# mcu.net
KiCad netlist of a schematic drawn in Altium Designer
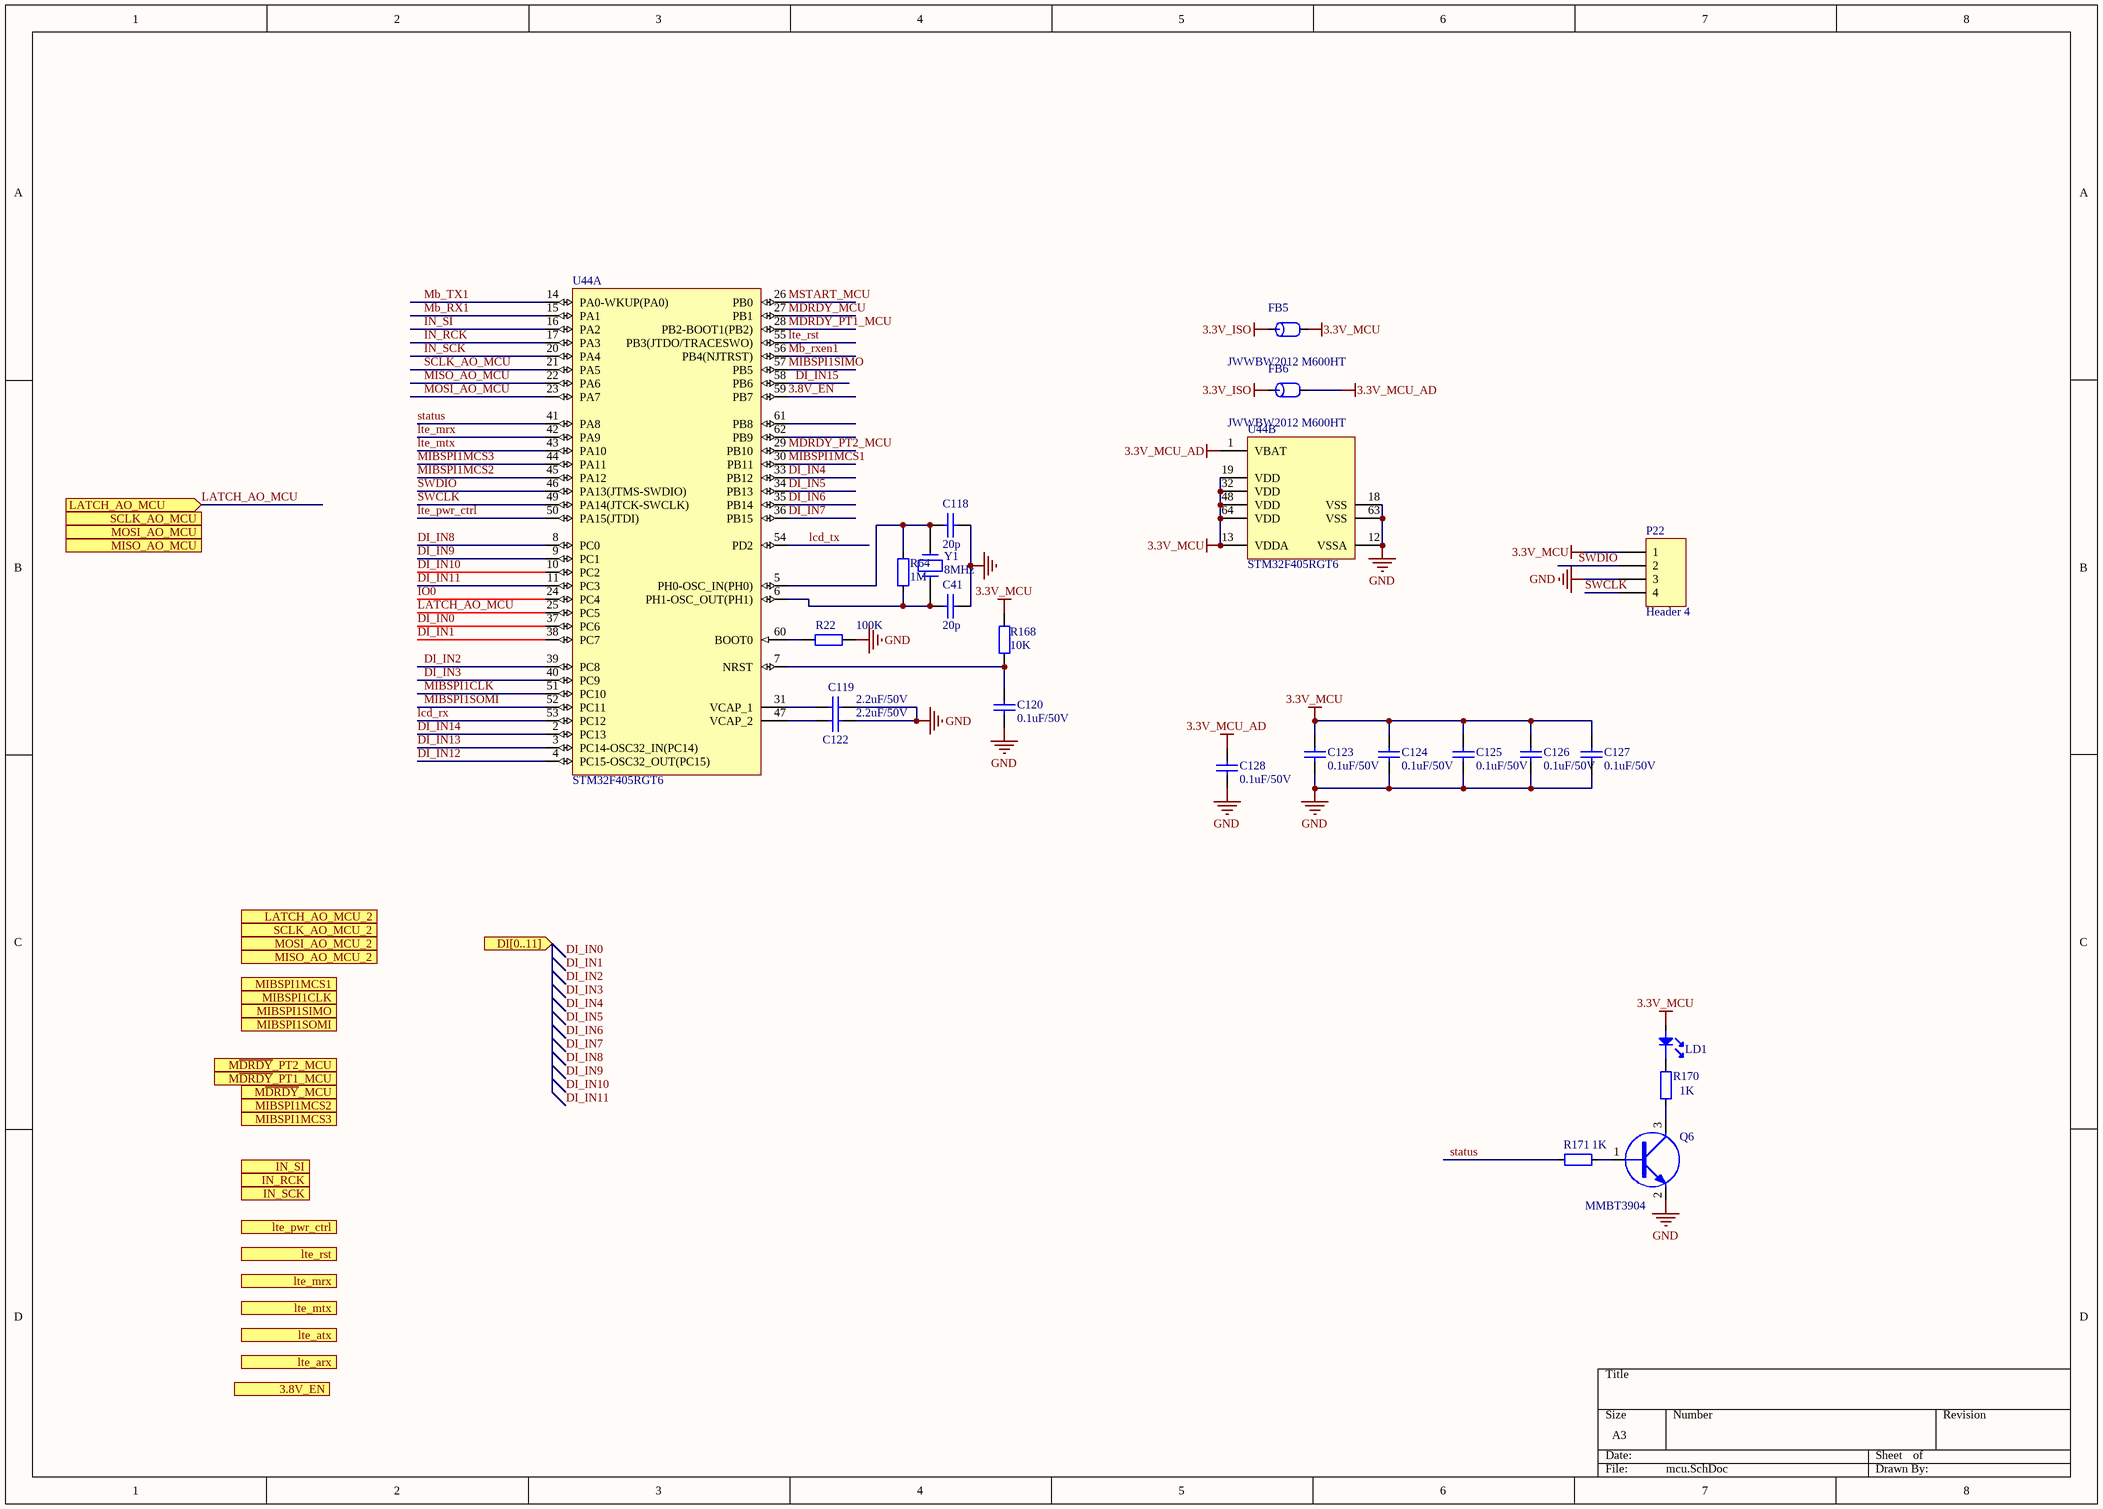
[diagram p0: mcu.SchDoc]

(export (version "E")
  (design (tool "Eeschema 10.0.6"))
  (components
    (comp (ref "C41")
      (value "20p")
      (footprint "0603c")
      (description "Capacitor")
      (libsource (lib "Schlib") (part "CAP"))
    )
    (comp (ref "C118")
      (value "20p")
      (footprint "0603c")
      (description "Capacitor")
      (libsource (lib "Schlib") (part "CAP"))
    )
    (comp (ref "C119")
      (value "2.2uF/50V")
      (footprint "0603C")
      (description "Capacitor")
      (fields (field (name "PUBLISHER") "Altium Limited"))
      (libsource (lib "Miscellaneous Devices") (part "Cap"))
    )
    (comp (ref "C120")
      (value "0.1uF/50V")
      (footprint "0603C")
      (description "Capacitor")
      (fields (field (name "PUBLISHER") "Altium Limited"))
      (libsource (lib "Miscellaneous Devices") (part "Cap"))
    )
    (comp (ref "C122")
      (value "2.2uF/50V")
      (footprint "0603C")
      (description "Capacitor")
      (fields (field (name "PUBLISHER") "Altium Limited"))
      (libsource (lib "Miscellaneous Devices") (part "Cap"))
    )
    (comp (ref "C123")
      (value "0.1uF/50V")
      (footprint "0603C")
      (description "Capacitor")
      (fields (field (name "PUBLISHER") "Altium Limited"))
      (libsource (lib "Miscellaneous Devices") (part "Cap"))
    )
    (comp (ref "C124")
      (value "0.1uF/50V")
      (footprint "0603C")
      (description "Capacitor")
      (fields (field (name "PUBLISHER") "Altium Limited"))
      (libsource (lib "Miscellaneous Devices") (part "Cap"))
    )
    (comp (ref "C125")
      (value "0.1uF/50V")
      (footprint "0603C")
      (description "Capacitor")
      (fields (field (name "PUBLISHER") "Altium Limited"))
      (libsource (lib "Miscellaneous Devices") (part "Cap"))
    )
    (comp (ref "C126")
      (value "0.1uF/50V")
      (footprint "0603C")
      (description "Capacitor")
      (fields (field (name "PUBLISHER") "Altium Limited"))
      (libsource (lib "Miscellaneous Devices") (part "Cap"))
    )
    (comp (ref "C127")
      (value "0.1uF/50V")
      (footprint "0603C")
      (description "Capacitor")
      (fields (field (name "PUBLISHER") "Altium Limited"))
      (libsource (lib "Miscellaneous Devices") (part "Cap"))
    )
    (comp (ref "C128")
      (value "0.1uF/50V")
      (footprint "0603C")
      (description "Capacitor")
      (fields (field (name "PUBLISHER") "Altium Limited"))
      (libsource (lib "Miscellaneous Devices") (part "Cap"))
    )
    (comp (ref "FB5")
      (value "JWWBW2012 M600HT")
      (footprint "0805R")
      (libsource (lib "Schlib_20110825") (part "FB"))
    )
    (comp (ref "FB6")
      (value "JWWBW2012 M600HT")
      (footprint "0805R")
      (libsource (lib "Schlib_20110825") (part "FB"))
    )
    (comp (ref "LD1")
      (value "LED_Green_19-217")
      (footprint "0603led")
      (libsource (lib "RC_M_D_00") (part "LED_Green_19-217"))
    )
    (comp (ref "P22")
      (value "Header 4")
      (footprint "HDR1X4")
      (description "Header, 4-Pin")
      (fields (field (name "PUBLISHER") "Altium Limited"))
      (libsource (lib "Miscellaneous Connectors") (part "Header 4"))
    )
    (comp (ref "Q6")
      (value "MMBT3904")
      (footprint "SOT23-3")
      (libsource (lib "CenLib") (part "NPN_MMBT3904"))
    )
    (comp (ref "R22") (value "100K") (footprint "0603R") (libsource (lib "") (part "Res0805M_1")))
    (comp (ref "R64") (value "1M") (footprint "0603R") (libsource (lib "RC_M_D_00") (part "RES0603")))
    (comp (ref "R168") (value "10K") (footprint "0603R") (libsource (lib "MQlibrary") (part "Res0805M")))
    (comp (ref "R170") (value "1K") (footprint "0603r") (libsource (lib "RC_M_D_00") (part "RES0603")))
    (comp (ref "R171") (value "1K") (footprint "0603r") (libsource (lib "RC_M_D_00") (part "RES0603")))
    (comp (ref "U44")
      (value "STM32F405RGT6")
      (footprint "LQFP-64")
      (fields (field (name "MANUFACTURER") "STMicroelectronics"))
      (libsource (lib "STMicroelectronics STM32 F4") (part "STM32F405RGT6"))
    )
    (comp (ref "Y1")
      (value "8MHz")
      (footprint "CRAY_5032")
      (description "HC49S-8MHz")
      (libsource (lib "*") (part "CRYSTAL"))
    )
  )
  (nets
    (net (code "13") (name "/3.8V_EN") (class "Default")
      (node (ref "U44") (pin "59") (pinfunction "PB7_59") (pintype "bidirectional"))
    )
    (net (code "15") (name "/DI_IN0") (class "Default")
      (node (ref "U44") (pin "37") (pinfunction "PC6_37") (pintype "bidirectional"))
    )
    (net (code "16") (name "/DI_IN1") (class "Default")
      (node (ref "U44") (pin "38") (pinfunction "PC7_38") (pintype "bidirectional"))
    )
    (net (code "17") (name "/DI_IN2") (class "Default")
      (node (ref "U44") (pin "39") (pinfunction "PC8_39") (pintype "bidirectional"))
    )
    (net (code "18") (name "/DI_IN3") (class "Default")
      (node (ref "U44") (pin "40") (pinfunction "PC9_40") (pintype "bidirectional"))
    )
    (net (code "19") (name "/DI_IN4") (class "Default")
      (node (ref "U44") (pin "33") (pinfunction "PB12_33") (pintype "bidirectional"))
    )
    (net (code "20") (name "/DI_IN5") (class "Default")
      (node (ref "U44") (pin "34") (pinfunction "PB13_34") (pintype "bidirectional"))
    )
    (net (code "21") (name "/DI_IN6") (class "Default")
      (node (ref "U44") (pin "35") (pinfunction "PB14_35") (pintype "bidirectional"))
    )
    (net (code "22") (name "/DI_IN7") (class "Default")
      (node (ref "U44") (pin "36") (pinfunction "PB15_36") (pintype "bidirectional"))
    )
    (net (code "23") (name "/DI_IN8") (class "Default")
      (node (ref "U44") (pin "8") (pinfunction "PC0_8") (pintype "bidirectional"))
    )
    (net (code "24") (name "/DI_IN9") (class "Default")
      (node (ref "U44") (pin "9") (pinfunction "PC1_9") (pintype "bidirectional"))
    )
    (net (code "25") (name "/DI_IN10") (class "Default")
      (node (ref "U44") (pin "10") (pinfunction "PC2_10") (pintype "bidirectional"))
    )
    (net (code "26") (name "/DI_IN11") (class "Default")
      (node (ref "U44") (pin "11") (pinfunction "PC3_11") (pintype "bidirectional"))
    )
    (net (code "27") (name "/DI_IN12") (class "Default")
      (node (ref "U44") (pin "4") (pinfunction "PC15-OSC32_OUT(PC15)_4") (pintype "bidirectional"))
    )
    (net (code "28") (name "/DI_IN13") (class "Default")
      (node (ref "U44") (pin "3") (pinfunction "PC14-OSC32_IN(PC14)_3") (pintype "bidirectional"))
    )
    (net (code "29") (name "/DI_IN14") (class "Default")
      (node (ref "U44") (pin "2") (pinfunction "PC13_2") (pintype "bidirectional"))
    )
    (net (code "30") (name "/DI_IN15") (class "Default")
      (node (ref "U44") (pin "58") (pinfunction "PB6_58") (pintype "bidirectional"))
    )
    (net (code "31") (name "/IN_RCK") (class "Default")
      (node (ref "U44") (pin "17") (pinfunction "PA3_17") (pintype "bidirectional"))
    )
    (net (code "32") (name "/IN_SCK") (class "Default")
      (node (ref "U44") (pin "20") (pinfunction "PA4_20") (pintype "bidirectional"))
    )
    (net (code "33") (name "/IN_SI") (class "Default")
      (node (ref "U44") (pin "16") (pinfunction "PA2_16") (pintype "bidirectional"))
    )
    (net (code "34") (name "/IO0") (class "Default")
      (node (ref "U44") (pin "24") (pinfunction "PC4_24") (pintype "bidirectional"))
    )
    (net (code "35") (name "/LATCH_AO_MCU") (class "Default")
      (node (ref "U44") (pin "25") (pinfunction "PC5_25") (pintype "bidirectional"))
    )
    (net (code "37") (name "/MIBSPI1CLK") (class "Default")
      (node (ref "U44") (pin "51") (pinfunction "PC10_51") (pintype "bidirectional"))
    )
    (net (code "38") (name "/MIBSPI1MCS1") (class "Default")
      (node (ref "U44") (pin "30") (pinfunction "PB11_30") (pintype "bidirectional"))
    )
    (net (code "39") (name "/MIBSPI1MCS2") (class "Default")
      (node (ref "U44") (pin "45") (pinfunction "PA12_45") (pintype "bidirectional"))
    )
    (net (code "40") (name "/MIBSPI1MCS3") (class "Default")
      (node (ref "U44") (pin "44") (pinfunction "PA11_44") (pintype "bidirectional"))
    )
    (net (code "41") (name "/MIBSPI1SIMO") (class "Default")
      (node (ref "U44") (pin "57") (pinfunction "PB5_57") (pintype "bidirectional"))
    )
    (net (code "42") (name "/MIBSPI1SOMI") (class "Default")
      (node (ref "U44") (pin "52") (pinfunction "PC11_52") (pintype "bidirectional"))
    )
    (net (code "43") (name "/MISO_AO_MCU") (class "Default")
      (node (ref "U44") (pin "22") (pinfunction "PA6_22") (pintype "bidirectional"))
    )
    (net (code "45") (name "/MOSI_AO_MCU") (class "Default")
      (node (ref "U44") (pin "23") (pinfunction "PA7_23") (pintype "bidirectional"))
    )
    (net (code "47") (name "/MSTART_MCU") (class "Default")
      (node (ref "U44") (pin "26") (pinfunction "PB0_26") (pintype "bidirectional"))
    )
    (net (code "48") (name "/Mb_RX1") (class "Default")
      (node (ref "U44") (pin "15") (pinfunction "PA1_15") (pintype "bidirectional"))
    )
    (net (code "49") (name "/Mb_TX1") (class "Default")
      (node (ref "U44") (pin "14") (pinfunction "PA0-WKUP(PA0)_14") (pintype "bidirectional"))
    )
    (net (code "50") (name "/Mb_rxen1") (class "Default")
      (node (ref "U44") (pin "56") (pinfunction "PB4(NJTRST)_56") (pintype "bidirectional"))
    )
    (net (code "51") (name "/M~{DRDY}_MCU") (class "Default")
      (node (ref "U44") (pin "27") (pinfunction "PB1_27") (pintype "bidirectional"))
    )
    (net (code "52") (name "/M~{DRDY}_PT1_MCU") (class "Default")
      (node (ref "U44") (pin "28") (pinfunction "PB2-BOOT1(PB2)_28") (pintype "bidirectional"))
    )
    (net (code "53") (name "/M~{DRDY}_PT2_MCU") (class "Default")
      (node (ref "U44") (pin "29") (pinfunction "PB10_29") (pintype "bidirectional"))
    )
    (net (code "54") (name "/SCLK_AO_MCU") (class "Default")
      (node (ref "U44") (pin "21") (pinfunction "PA5_21") (pintype "bidirectional"))
    )
    (net (code "56") (name "/SWCLK") (class "Default")
      (node (ref "P22") (pin "4") (pinfunction "4_4") (pintype "passive"))
      (node (ref "U44") (pin "49") (pinfunction "PA14(JTCK-SWCLK)_49") (pintype "bidirectional"))
    )
    (net (code "57") (name "/SWDIO") (class "Default")
      (node (ref "P22") (pin "2") (pinfunction "2_2") (pintype "passive"))
      (node (ref "U44") (pin "46") (pinfunction "PA13(JTMS-SWDIO)_46") (pintype "bidirectional"))
    )
    (net (code "58") (name "/lcd_rx") (class "Default")
      (node (ref "U44") (pin "53") (pinfunction "PC12_53") (pintype "bidirectional"))
    )
    (net (code "59") (name "/lcd_tx") (class "Default")
      (node (ref "U44") (pin "54") (pinfunction "PD2_54") (pintype "bidirectional"))
    )
    (net (code "62") (name "/lte_mrx") (class "Default")
      (node (ref "U44") (pin "42") (pinfunction "PA9_42") (pintype "bidirectional"))
    )
    (net (code "63") (name "/lte_mtx") (class "Default")
      (node (ref "U44") (pin "43") (pinfunction "PA10_43") (pintype "bidirectional"))
    )
    (net (code "64") (name "/lte_pwr_ctrl") (class "Default")
      (node (ref "U44") (pin "50") (pinfunction "PA15(JTDI)_50") (pintype "bidirectional"))
    )
    (net (code "65") (name "/lte_rst") (class "Default")
      (node (ref "U44") (pin "55") (pinfunction "PB3(JTDO/TRACESWO)_55") (pintype "bidirectional"))
    )
    (net (code "66") (name "/status") (class "Default")
      (node (ref "R171") (pin "1") (pinfunction "1_1") (pintype "passive"))
      (node (ref "U44") (pin "41") (pinfunction "PA8_41") (pintype "bidirectional"))
    )
    (net (code "67") (name "3.3V_ISO") (class "Default")
      (node (ref "FB5") (pin "1") (pintype "passive"))
      (node (ref "FB6") (pin "1") (pintype "passive"))
    )
    (net (code "68") (name "3.3V_MCU") (class "Default")
      (node (ref "C123") (pin "2") (pinfunction "2_2") (pintype "passive"))
      (node (ref "C124") (pin "2") (pinfunction "2_2") (pintype "passive"))
      (node (ref "C125") (pin "2") (pinfunction "2_2") (pintype "passive"))
      (node (ref "C126") (pin "2") (pinfunction "2_2") (pintype "passive"))
      (node (ref "C127") (pin "2") (pinfunction "2_2") (pintype "passive"))
      (node (ref "FB5") (pin "2") (pintype "passive"))
      (node (ref "LD1") (pin "1") (pinfunction "1_1") (pintype "passive"))
      (node (ref "P22") (pin "1") (pinfunction "1_1") (pintype "passive"))
      (node (ref "R168") (pin "2") (pinfunction "2_2") (pintype "passive"))
      (node (ref "U44") (pin "13") (pinfunction "VDDA_13") (pintype "power_in"))
      (node (ref "U44") (pin "19") (pinfunction "VDD_19") (pintype "power_in"))
      (node (ref "U44") (pin "32") (pinfunction "VDD_32") (pintype "power_in"))
      (node (ref "U44") (pin "48") (pinfunction "VDD_48") (pintype "power_in"))
      (node (ref "U44") (pin "64") (pinfunction "VDD_64") (pintype "power_in"))
    )
    (net (code "69") (name "3.3V_MCU_AD") (class "Default")
      (node (ref "C128") (pin "2") (pinfunction "2_2") (pintype "passive"))
      (node (ref "FB6") (pin "2") (pintype "passive"))
      (node (ref "U44") (pin "1") (pinfunction "VBAT_1") (pintype "power_in"))
    )
    (net (code "70") (name "GND") (class "Default")
      (node (ref "C118") (pin "1") (pinfunction "1_1") (pintype "passive"))
      (node (ref "C119") (pin "1") (pinfunction "1_1") (pintype "passive"))
      (node (ref "C120") (pin "1") (pinfunction "1_1") (pintype "passive"))
      (node (ref "C122") (pin "1") (pinfunction "1_1") (pintype "passive"))
      (node (ref "C123") (pin "1") (pinfunction "1_1") (pintype "passive"))
      (node (ref "C124") (pin "1") (pinfunction "1_1") (pintype "passive"))
      (node (ref "C125") (pin "1") (pinfunction "1_1") (pintype "passive"))
      (node (ref "C126") (pin "1") (pinfunction "1_1") (pintype "passive"))
      (node (ref "C127") (pin "1") (pinfunction "1_1") (pintype "passive"))
      (node (ref "C128") (pin "1") (pinfunction "1_1") (pintype "passive"))
      (node (ref "C41") (pin "1") (pinfunction "1_1") (pintype "passive"))
      (node (ref "P22") (pin "3") (pinfunction "3_3") (pintype "passive"))
      (node (ref "Q6") (pin "2") (pinfunction "E_2") (pintype "passive"))
      (node (ref "R22") (pin "2") (pinfunction "2_2") (pintype "passive"))
      (node (ref "U44") (pin "12") (pinfunction "VSSA_12") (pintype "power_in"))
      (node (ref "U44") (pin "18") (pinfunction "VSS_18") (pintype "power_in"))
      (node (ref "U44") (pin "63") (pinfunction "VSS_63") (pintype "power_in"))
    )
    (net (code "71") (name "Net-(LD1-Pad2)") (class "Default")
      (node (ref "LD1") (pin "2") (pinfunction "2_2") (pintype "passive"))
      (node (ref "R170") (pin "1") (pinfunction "1_1") (pintype "passive"))
    )
    (net (code "72") (name "Net-(Q6-B)") (class "Default")
      (node (ref "Q6") (pin "1") (pinfunction "B_1") (pintype "passive"))
      (node (ref "R171") (pin "2") (pinfunction "2_2") (pintype "passive"))
    )
    (net (code "73") (name "Net-(Q6-C)") (class "Default")
      (node (ref "Q6") (pin "3") (pinfunction "C_3") (pintype "passive"))
      (node (ref "R170") (pin "2") (pinfunction "2_2") (pintype "passive"))
    )
    (net (code "74") (name "Net-(U44A-BOOT0)") (class "Default")
      (node (ref "R22") (pin "1") (pinfunction "1_1") (pintype "passive"))
      (node (ref "U44") (pin "60") (pinfunction "BOOT0_60") (pintype "input"))
    )
    (net (code "75") (name "Net-(U44A-NRST)") (class "Default")
      (node (ref "C120") (pin "2") (pinfunction "2_2") (pintype "passive"))
      (node (ref "R168") (pin "1") (pinfunction "1_1") (pintype "passive"))
      (node (ref "U44") (pin "7") (pinfunction "NRST_7") (pintype "bidirectional"))
    )
    (net (code "76") (name "Net-(U44A-PH0-OSC_IN(PH0))") (class "Default")
      (node (ref "C118") (pin "2") (pinfunction "2_2") (pintype "passive"))
      (node (ref "R64") (pin "2") (pinfunction "2_2") (pintype "passive"))
      (node (ref "U44") (pin "5") (pinfunction "PH0-OSC_IN(PH0)_5") (pintype "bidirectional"))
      (node (ref "Y1") (pin "1") (pinfunction "1_1") (pintype "passive"))
    )
    (net (code "77") (name "Net-(U44A-PH1-OSC_OUT(PH1))") (class "Default")
      (node (ref "C41") (pin "2") (pinfunction "2_2") (pintype "passive"))
      (node (ref "R64") (pin "1") (pinfunction "1_1") (pintype "passive"))
      (node (ref "U44") (pin "6") (pinfunction "PH1-OSC_OUT(PH1)_6") (pintype "bidirectional"))
      (node (ref "Y1") (pin "2") (pinfunction "2_2") (pintype "passive"))
    )
    (net (code "78") (name "Net-(U44A-VCAP_1)") (class "Default")
      (node (ref "C119") (pin "2") (pinfunction "2_2") (pintype "passive"))
      (node (ref "U44") (pin "31") (pinfunction "VCAP_1_31") (pintype "power_in"))
    )
    (net (code "79") (name "Net-(U44A-VCAP_2)") (class "Default")
      (node (ref "C122") (pin "2") (pinfunction "2_2") (pintype "passive"))
      (node (ref "U44") (pin "47") (pinfunction "VCAP_2_47") (pintype "power_in"))
    )
    (net (code "80") (name "unconnected-(U44A-PB8-Pad61)") (class "Default")
      (node (ref "U44") (pin "61") (pinfunction "PB8_61") (pintype "bidirectional"))
    )
    (net (code "81") (name "unconnected-(U44A-PB9-Pad62)") (class "Default")
      (node (ref "U44") (pin "62") (pinfunction "PB9_62") (pintype "bidirectional"))
    )
  )
)
